# STM32F401R.net
KiCad netlist of a schematic drawn in Altium Designer
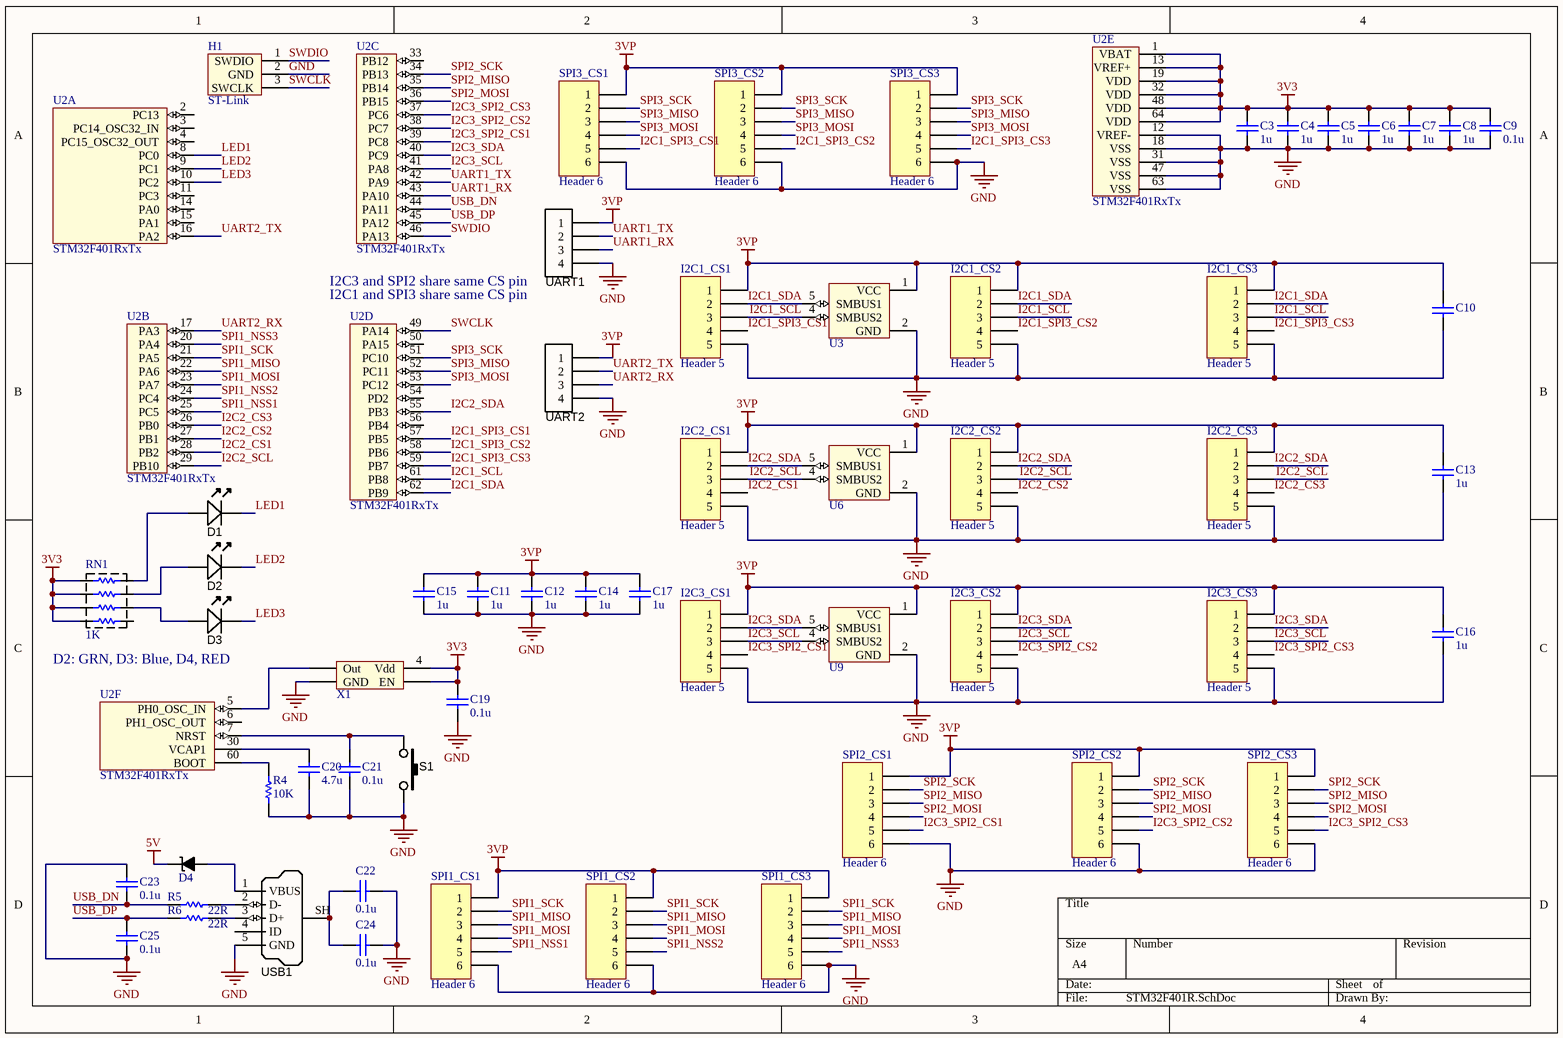
[diagram p0: STM32F401R.SchDoc]

(export (version "E")
  (design (tool "Eeschema 10.0.6"))
  (components
    (comp (ref "C3")
      (value "1u")
      (footprint "CAPC1608X90N")
      (description "Capacitor")
      (fields (field (name "Comment") "Cap") (field (name "PUBLISHER") "Altium Limited"))
      (libsource (lib "IOBoard_Low") (part "Cap"))
    )
    (comp (ref "C4")
      (value "1u")
      (footprint "CAPC1608X90N")
      (description "Capacitor")
      (fields (field (name "Comment") "Cap") (field (name "PUBLISHER") "Altium Limited"))
      (libsource (lib "IOBoard_Low") (part "Cap"))
    )
    (comp (ref "C5")
      (value "1u")
      (footprint "CAPC1608X90N")
      (description "Capacitor")
      (fields (field (name "Comment") "Cap") (field (name "PUBLISHER") "Altium Limited"))
      (libsource (lib "IOBoard_Low") (part "Cap"))
    )
    (comp (ref "C6")
      (value "1u")
      (footprint "CAPC1608X90N")
      (description "Capacitor")
      (fields (field (name "Comment") "Cap") (field (name "PUBLISHER") "Altium Limited"))
      (libsource (lib "IOBoard_Low") (part "Cap"))
    )
    (comp (ref "C7")
      (value "1u")
      (footprint "CAPC1608X90N")
      (description "Capacitor")
      (fields (field (name "Comment") "Cap") (field (name "PUBLISHER") "Altium Limited"))
      (libsource (lib "IOBoard_Low") (part "Cap"))
    )
    (comp (ref "C8")
      (value "1u")
      (footprint "CAPC1608X90N")
      (description "Capacitor")
      (fields (field (name "Comment") "Cap") (field (name "PUBLISHER") "Altium Limited"))
      (libsource (lib "IOBoard_Low") (part "Cap"))
    )
    (comp (ref "C9")
      (value "0.1u")
      (footprint "CAPC1608X90N")
      (description "Capacitor")
      (fields (field (name "Comment") "Cap") (field (name "PUBLISHER") "Altium Limited"))
      (libsource (lib "IOBoard_Low") (part "Cap"))
    )
    (comp (ref "C10")
      (value "Cap")
      (footprint "CAPC1608X90N")
      (description "Capacitor")
      (fields (field (name "PUBLISHER") "Altium Limited"))
      (libsource (lib "IOBoard_Low") (part "Cap"))
    )
    (comp (ref "C11")
      (value "1u")
      (footprint "CAPC1608X90N")
      (description "Capacitor")
      (fields (field (name "Comment") "Cap") (field (name "PUBLISHER") "Altium Limited"))
      (libsource (lib "IOBoard_Low") (part "Cap"))
    )
    (comp (ref "C12")
      (value "1u")
      (footprint "CAPC1608X90N")
      (description "Capacitor")
      (fields (field (name "Comment") "Cap") (field (name "PUBLISHER") "Altium Limited"))
      (libsource (lib "IOBoard_Low") (part "Cap"))
    )
    (comp (ref "C13")
      (value "1u")
      (footprint "CAPC1608X90N")
      (description "Capacitor")
      (fields (field (name "Comment") "Cap") (field (name "PUBLISHER") "Altium Limited"))
      (libsource (lib "IOBoard_Low") (part "Cap"))
    )
    (comp (ref "C14")
      (value "1u")
      (footprint "CAPC1608X90N")
      (description "Capacitor")
      (fields (field (name "Comment") "Cap") (field (name "PUBLISHER") "Altium Limited"))
      (libsource (lib "IOBoard_Low") (part "Cap"))
    )
    (comp (ref "C15")
      (value "1u")
      (footprint "CAPC1608X90N")
      (description "Capacitor")
      (fields (field (name "Comment") "Cap") (field (name "PUBLISHER") "Altium Limited"))
      (libsource (lib "IOBoard_Low") (part "Cap"))
    )
    (comp (ref "C16")
      (value "1u")
      (footprint "CAPC1608X90N")
      (description "Capacitor")
      (fields (field (name "Comment") "Cap") (field (name "PUBLISHER") "Altium Limited"))
      (libsource (lib "IOBoard_Low") (part "Cap"))
    )
    (comp (ref "C17")
      (value "1u")
      (footprint "CAPC1608X90N")
      (description "Capacitor")
      (fields (field (name "Comment") "Cap") (field (name "PUBLISHER") "Altium Limited"))
      (libsource (lib "IOBoard_Low") (part "Cap"))
    )
    (comp (ref "C19")
      (value "0.1u")
      (footprint "CAPC1608X90N")
      (description "Capacitor")
      (fields (field (name "Comment") "Cap") (field (name "PUBLISHER") "Altium Limited"))
      (libsource (lib "IOBoard_Low") (part "Cap"))
    )
    (comp (ref "C20")
      (value "4.7u")
      (footprint "CAPC1608X90N")
      (description "Capacitor")
      (fields (field (name "Comment") "Cap") (field (name "PUBLISHER") "Altium Limited"))
      (libsource (lib "IOBoard_Low") (part "Cap"))
    )
    (comp (ref "C21")
      (value "0.1u")
      (footprint "CAPC1608X90N")
      (description "Capacitor")
      (fields (field (name "Comment") "Cap") (field (name "PUBLISHER") "Altium Limited"))
      (libsource (lib "IOBoard_Low") (part "Cap"))
    )
    (comp (ref "C22")
      (value "0.1u")
      (footprint "CAPC1608X90N")
      (description "Capacitor")
      (fields (field (name "Comment") "Cap") (field (name "PUBLISHER") "Altium Limited"))
      (libsource (lib "IOBoard_Low") (part "Cap"))
    )
    (comp (ref "C23")
      (value "0.1u")
      (footprint "CAPC1608X90N")
      (description "Capacitor")
      (fields (field (name "Comment") "Cap") (field (name "PUBLISHER") "Altium Limited"))
      (libsource (lib "IOBoard_Low") (part "Cap"))
    )
    (comp (ref "C24")
      (value "0.1u")
      (footprint "CAPC1608X90N")
      (description "Capacitor")
      (fields (field (name "Comment") "Cap") (field (name "PUBLISHER") "Altium Limited"))
      (libsource (lib "IOBoard_Low") (part "Cap"))
    )
    (comp (ref "C25")
      (value "0.1u")
      (footprint "CAPC1608X90N")
      (description "Capacitor")
      (fields (field (name "Comment") "Cap") (field (name "PUBLISHER") "Altium Limited"))
      (libsource (lib "IOBoard_Low") (part "Cap"))
    )
    (comp (ref "D1")
      (value "LED_Green_GullWing")
      (footprint "LED-0805-A")
      (description "LED Gull-wing SMD High-intensity Green 450mcd 574nm")
      (libsource (lib "IOBoard") (part "LED_Green_GullWing"))
    )
    (comp (ref "D2")
      (value "LED_Green_GullWing")
      (footprint "LED-0805-A")
      (description "LED Gull-wing SMD High-intensity Green 450mcd 574nm")
      (libsource (lib "IOBoard") (part "LED_Green_GullWing"))
    )
    (comp (ref "D3")
      (value "LED_Green_GullWing")
      (footprint "LED-0805-A")
      (description "LED Gull-wing SMD High-intensity Green 450mcd 574nm")
      (libsource (lib "IOBoard") (part "LED_Green_GullWing"))
    )
    (comp (ref "D4")
      (value "MBRA210LT3G")
      (footprint "SMA")
      (description "Surface Mount  Schottky Power Rectifier")
      (fields (field (name "MANUFACTURER") "ON semiconductor"))
      (libsource (lib "IOBoard_Low") (part "MBRA210LT3G"))
    )
    (comp (ref "H1")
      (value "ST-Link")
      (footprint "ST-Link")
      (description "ST-Link header with silkscreen")
      (libsource (lib "IOBoard") (part "ST-Link"))
    )
    (comp (ref "I2C1_CS1")
      (value "Header 5")
      (footprint "HDR1X5")
      (description "Header, 5-Pin")
      (fields (field (name "PUBLISHER") "Altium Limited"))
      (libsource (lib "Miscellaneous Connectors") (part "Header 5"))
    )
    (comp (ref "I2C1_CS2")
      (value "Header 5")
      (footprint "HDR1X5")
      (description "Header, 5-Pin")
      (fields (field (name "PUBLISHER") "Altium Limited"))
      (libsource (lib "Miscellaneous Connectors") (part "Header 5"))
    )
    (comp (ref "I2C1_CS3")
      (value "Header 5")
      (footprint "HDR1X5")
      (description "Header, 5-Pin")
      (fields (field (name "PUBLISHER") "Altium Limited"))
      (libsource (lib "Miscellaneous Connectors") (part "Header 5"))
    )
    (comp (ref "I2C2_CS1")
      (value "Header 5")
      (footprint "HDR1X5")
      (description "Header, 5-Pin")
      (fields (field (name "PUBLISHER") "Altium Limited"))
      (libsource (lib "Miscellaneous Connectors") (part "Header 5"))
    )
    (comp (ref "I2C2_CS2")
      (value "Header 5")
      (footprint "HDR1X5")
      (description "Header, 5-Pin")
      (fields (field (name "PUBLISHER") "Altium Limited"))
      (libsource (lib "Miscellaneous Connectors") (part "Header 5"))
    )
    (comp (ref "I2C2_CS3")
      (value "Header 5")
      (footprint "HDR1X5")
      (description "Header, 5-Pin")
      (fields (field (name "PUBLISHER") "Altium Limited"))
      (libsource (lib "Miscellaneous Connectors") (part "Header 5"))
    )
    (comp (ref "I2C3_CS1")
      (value "Header 5")
      (footprint "HDR1X5")
      (description "Header, 5-Pin")
      (fields (field (name "PUBLISHER") "Altium Limited"))
      (libsource (lib "Miscellaneous Connectors") (part "Header 5"))
    )
    (comp (ref "I2C3_CS2")
      (value "Header 5")
      (footprint "HDR1X5")
      (description "Header, 5-Pin")
      (fields (field (name "PUBLISHER") "Altium Limited"))
      (libsource (lib "Miscellaneous Connectors") (part "Header 5"))
    )
    (comp (ref "I2C3_CS3")
      (value "Header 5")
      (footprint "HDR1X5")
      (description "Header, 5-Pin")
      (fields (field (name "PUBLISHER") "Altium Limited"))
      (libsource (lib "Miscellaneous Connectors") (part "Header 5"))
    )
    (comp (ref "R4")
      (value "10K")
      (footprint "RESC1608X55N")
      (description "Resistor")
      (fields (field (name "Comment") "Res1") (field (name "PUBLISHER") "Altium Limited"))
      (libsource (lib "IOBoard_Low") (part "Res1"))
    )
    (comp (ref "R5")
      (value "22R")
      (footprint "RESC1608X55N")
      (description "Resistor")
      (fields (field (name "Comment") "Res1") (field (name "PUBLISHER") "Altium Limited"))
      (libsource (lib "IOBoard_Low") (part "Res1"))
    )
    (comp (ref "R6")
      (value "22R")
      (footprint "RESC1608X55N")
      (description "Resistor")
      (fields (field (name "Comment") "Res1") (field (name "PUBLISHER") "Altium Limited"))
      (libsource (lib "IOBoard_Low") (part "Res1"))
    )
    (comp (ref "RN1")
      (value "1K")
      (footprint "RESCAXS50P160X320X70-8N")
      (fields (field (name "Comment") "resistor network"))
      (libsource (lib "IOBoard") (part "RES_NET"))
    )
    (comp (ref "S1")
      (value "SW_THT_PB_4.3mm")
      (footprint "TACT_SWT-SMD-4.4")
      (description "Switch, tact, 4.3mm stem")
      (libsource (lib "IOBoard") (part "SW_THT_PB_4.3mm"))
    )
    (comp (ref "SPI1_CS1")
      (value "Header 6")
      (footprint "HDR1X6")
      (description "Header, 6-Pin")
      (fields (field (name "PUBLISHER") "Altium Limited"))
      (libsource (lib "Miscellaneous Connectors") (part "Header 6"))
    )
    (comp (ref "SPI1_CS2")
      (value "Header 6")
      (footprint "HDR1X6")
      (description "Header, 6-Pin")
      (fields (field (name "PUBLISHER") "Altium Limited"))
      (libsource (lib "Miscellaneous Connectors") (part "Header 6"))
    )
    (comp (ref "SPI1_CS3")
      (value "Header 6")
      (footprint "HDR1X6")
      (description "Header, 6-Pin")
      (fields (field (name "PUBLISHER") "Altium Limited"))
      (libsource (lib "Miscellaneous Connectors") (part "Header 6"))
    )
    (comp (ref "SPI2_CS1")
      (value "Header 6")
      (footprint "HDR1X6")
      (description "Header, 6-Pin")
      (fields (field (name "PUBLISHER") "Altium Limited"))
      (libsource (lib "Miscellaneous Connectors") (part "Header 6"))
    )
    (comp (ref "SPI2_CS2")
      (value "Header 6")
      (footprint "HDR1X6")
      (description "Header, 6-Pin")
      (fields (field (name "PUBLISHER") "Altium Limited"))
      (libsource (lib "Miscellaneous Connectors") (part "Header 6"))
    )
    (comp (ref "SPI2_CS3")
      (value "Header 6")
      (footprint "HDR1X6")
      (description "Header, 6-Pin")
      (fields (field (name "PUBLISHER") "Altium Limited"))
      (libsource (lib "Miscellaneous Connectors") (part "Header 6"))
    )
    (comp (ref "SPI3_CS1")
      (value "Header 6")
      (footprint "HDR1X6")
      (description "Header, 6-Pin")
      (fields (field (name "PUBLISHER") "Altium Limited"))
      (libsource (lib "Miscellaneous Connectors") (part "Header 6"))
    )
    (comp (ref "SPI3_CS2")
      (value "Header 6")
      (footprint "HDR1X6")
      (description "Header, 6-Pin")
      (fields (field (name "PUBLISHER") "Altium Limited"))
      (libsource (lib "Miscellaneous Connectors") (part "Header 6"))
    )
    (comp (ref "SPI3_CS3")
      (value "Header 6")
      (footprint "HDR1X6")
      (description "Header, 6-Pin")
      (fields (field (name "PUBLISHER") "Altium Limited"))
      (libsource (lib "Miscellaneous Connectors") (part "Header 6"))
    )
    (comp (ref "U2")
      (value "STM32F401RxTx")
      (footprint "LQFP64")
      (libsource (lib "IOBoard") (part "STM32F401RxTx"))
    )
    (comp (ref "U3") (value "LTC1694") (footprint "SOT23-5") (libsource (lib "IOBoard") (part "LTC1694")))
    (comp (ref "U6") (value "LTC1694") (footprint "SOT23-5") (libsource (lib "IOBoard") (part "LTC1694")))
    (comp (ref "U9") (value "LTC1694") (footprint "SOT23-5") (libsource (lib "IOBoard") (part "LTC1694")))
    (comp (ref "UART1")
      (value "Programmer")
      (footprint "HDR1X4_2.54MMP")
      (description "Header 4-pin")
      (libsource (lib "IOBoard") (part "Header4P"))
    )
    (comp (ref "UART2")
      (value "Programmer")
      (footprint "HDR1X4_2.54MMP")
      (description "Header 4-pin")
      (libsource (lib "IOBoard") (part "Header4P"))
    )
    (comp (ref "USB1")
      (value "USB Micro Type B")
      (footprint "USB_MICRO-B")
      (description "Connector SMD USB Micro Type B middle mount")
      (libsource (lib "IOBoard") (part "USB_Micro_TypeB"))
    )
    (comp (ref "X1")
      (value "ASV-8.000MHZ-EJ-T")
      (footprint "ASV SERIES")
      (description "3.3Vdc HCMOS SMD Crystal Clock Oscillator")
      (fields (field (name "MANUFACTURER") "Abracon"))
      (libsource (lib "IOBoard") (part "ASV-8.000MHZ-EJ-T"))
    )
  )
  (nets
    (net (code "1") (name "/I2C1_SCL") (class "Default")
      (node (ref "I2C1_CS1") (pin "3") (pinfunction "3_3") (pintype "passive"))
      (node (ref "I2C1_CS2") (pin "3") (pinfunction "3_3") (pintype "passive"))
      (node (ref "I2C1_CS3") (pin "3") (pinfunction "3_3") (pintype "passive"))
      (node (ref "U2") (pin "61") (pinfunction "PB8_61") (pintype "bidirectional"))
      (node (ref "U3") (pin "4") (pinfunction "SMBUS2_4") (pintype "bidirectional"))
    )
    (net (code "2") (name "/I2C1_SDA") (class "Default")
      (node (ref "I2C1_CS1") (pin "2") (pinfunction "2_2") (pintype "passive"))
      (node (ref "I2C1_CS2") (pin "2") (pinfunction "2_2") (pintype "passive"))
      (node (ref "I2C1_CS3") (pin "2") (pinfunction "2_2") (pintype "passive"))
      (node (ref "U2") (pin "62") (pinfunction "PB9_62") (pintype "bidirectional"))
      (node (ref "U3") (pin "5") (pinfunction "SMBUS1_5") (pintype "bidirectional"))
    )
    (net (code "3") (name "/I2C1_SPI3_CS1") (class "Default")
      (node (ref "I2C1_CS1") (pin "4") (pinfunction "4_4") (pintype "passive"))
      (node (ref "SPI3_CS1") (pin "5") (pinfunction "5_5") (pintype "passive"))
      (node (ref "U2") (pin "57") (pinfunction "PB5_57") (pintype "bidirectional"))
    )
    (net (code "4") (name "/I2C1_SPI3_CS2") (class "Default")
      (node (ref "I2C1_CS2") (pin "4") (pinfunction "4_4") (pintype "passive"))
      (node (ref "SPI3_CS2") (pin "5") (pinfunction "5_5") (pintype "passive"))
      (node (ref "U2") (pin "58") (pinfunction "PB6_58") (pintype "bidirectional"))
    )
    (net (code "5") (name "/I2C1_SPI3_CS3") (class "Default")
      (node (ref "I2C1_CS3") (pin "4") (pinfunction "4_4") (pintype "passive"))
      (node (ref "SPI3_CS3") (pin "5") (pinfunction "5_5") (pintype "passive"))
      (node (ref "U2") (pin "59") (pinfunction "PB7_59") (pintype "bidirectional"))
    )
    (net (code "6") (name "/I2C2_CS1") (class "Default")
      (node (ref "I2C2_CS1") (pin "4") (pinfunction "4_4") (pintype "passive"))
      (node (ref "U2") (pin "28") (pinfunction "PB2_28") (pintype "bidirectional"))
    )
    (net (code "7") (name "/I2C2_CS2") (class "Default")
      (node (ref "I2C2_CS2") (pin "4") (pinfunction "4_4") (pintype "passive"))
      (node (ref "U2") (pin "27") (pinfunction "PB1_27") (pintype "bidirectional"))
    )
    (net (code "8") (name "/I2C2_CS3") (class "Default")
      (node (ref "I2C2_CS3") (pin "4") (pinfunction "4_4") (pintype "passive"))
      (node (ref "U2") (pin "26") (pinfunction "PB0_26") (pintype "bidirectional"))
    )
    (net (code "9") (name "/I2C2_SCL") (class "Default")
      (node (ref "I2C2_CS1") (pin "3") (pinfunction "3_3") (pintype "passive"))
      (node (ref "I2C2_CS2") (pin "3") (pinfunction "3_3") (pintype "passive"))
      (node (ref "I2C2_CS3") (pin "3") (pinfunction "3_3") (pintype "passive"))
      (node (ref "U2") (pin "29") (pinfunction "PB10_29") (pintype "bidirectional"))
      (node (ref "U6") (pin "4") (pinfunction "SMBUS2_4") (pintype "bidirectional"))
    )
    (net (code "10") (name "/I2C2_SDA") (class "Default")
      (node (ref "I2C2_CS1") (pin "2") (pinfunction "2_2") (pintype "passive"))
      (node (ref "I2C2_CS2") (pin "2") (pinfunction "2_2") (pintype "passive"))
      (node (ref "I2C2_CS3") (pin "2") (pinfunction "2_2") (pintype "passive"))
      (node (ref "U2") (pin "55") (pinfunction "PB3_55") (pintype "bidirectional"))
      (node (ref "U6") (pin "5") (pinfunction "SMBUS1_5") (pintype "bidirectional"))
    )
    (net (code "11") (name "/I2C3_SCL") (class "Default")
      (node (ref "I2C3_CS1") (pin "3") (pinfunction "3_3") (pintype "passive"))
      (node (ref "I2C3_CS2") (pin "3") (pinfunction "3_3") (pintype "passive"))
      (node (ref "I2C3_CS3") (pin "3") (pinfunction "3_3") (pintype "passive"))
      (node (ref "U2") (pin "41") (pinfunction "PA8_41") (pintype "bidirectional"))
      (node (ref "U9") (pin "4") (pinfunction "SMBUS2_4") (pintype "bidirectional"))
    )
    (net (code "12") (name "/I2C3_SDA") (class "Default")
      (node (ref "I2C3_CS1") (pin "2") (pinfunction "2_2") (pintype "passive"))
      (node (ref "I2C3_CS2") (pin "2") (pinfunction "2_2") (pintype "passive"))
      (node (ref "I2C3_CS3") (pin "2") (pinfunction "2_2") (pintype "passive"))
      (node (ref "U2") (pin "40") (pinfunction "PC9_40") (pintype "bidirectional"))
      (node (ref "U9") (pin "5") (pinfunction "SMBUS1_5") (pintype "bidirectional"))
    )
    (net (code "13") (name "/I2C3_SPI2_CS1") (class "Default")
      (node (ref "I2C3_CS1") (pin "4") (pinfunction "4_4") (pintype "passive"))
      (node (ref "SPI2_CS1") (pin "5") (pinfunction "5_5") (pintype "passive"))
      (node (ref "U2") (pin "39") (pinfunction "PC8_39") (pintype "bidirectional"))
    )
    (net (code "14") (name "/I2C3_SPI2_CS2") (class "Default")
      (node (ref "I2C3_CS2") (pin "4") (pinfunction "4_4") (pintype "passive"))
      (node (ref "SPI2_CS2") (pin "5") (pinfunction "5_5") (pintype "passive"))
      (node (ref "U2") (pin "38") (pinfunction "PC7_38") (pintype "bidirectional"))
    )
    (net (code "15") (name "/I2C3_SPI2_CS3") (class "Default")
      (node (ref "I2C3_CS3") (pin "4") (pinfunction "4_4") (pintype "passive"))
      (node (ref "SPI2_CS3") (pin "5") (pinfunction "5_5") (pintype "passive"))
      (node (ref "U2") (pin "37") (pinfunction "PC6_37") (pintype "bidirectional"))
    )
    (net (code "16") (name "/LED1") (class "Default")
      (node (ref "D1") (pin "K") (pinfunction "K_K") (pintype "passive"))
      (node (ref "U2") (pin "8") (pinfunction "PC0_8") (pintype "bidirectional"))
    )
    (net (code "17") (name "/LED2") (class "Default")
      (node (ref "D2") (pin "K") (pinfunction "K_K") (pintype "passive"))
      (node (ref "U2") (pin "9") (pinfunction "PC1_9") (pintype "bidirectional"))
    )
    (net (code "18") (name "/LED3") (class "Default")
      (node (ref "D3") (pin "K") (pinfunction "K_K") (pintype "passive"))
      (node (ref "U2") (pin "10") (pinfunction "PC2_10") (pintype "bidirectional"))
    )
    (net (code "19") (name "/SPI1_MISO") (class "Default")
      (node (ref "SPI1_CS1") (pin "3") (pinfunction "3_3") (pintype "passive"))
      (node (ref "SPI1_CS2") (pin "3") (pinfunction "3_3") (pintype "passive"))
      (node (ref "SPI1_CS3") (pin "3") (pinfunction "3_3") (pintype "passive"))
      (node (ref "U2") (pin "22") (pinfunction "PA6_22") (pintype "bidirectional"))
    )
    (net (code "20") (name "/SPI1_MOSI") (class "Default")
      (node (ref "SPI1_CS1") (pin "4") (pinfunction "4_4") (pintype "passive"))
      (node (ref "SPI1_CS2") (pin "4") (pinfunction "4_4") (pintype "passive"))
      (node (ref "SPI1_CS3") (pin "4") (pinfunction "4_4") (pintype "passive"))
      (node (ref "U2") (pin "23") (pinfunction "PA7_23") (pintype "bidirectional"))
    )
    (net (code "21") (name "/SPI1_NSS1") (class "Default")
      (node (ref "SPI1_CS1") (pin "5") (pinfunction "5_5") (pintype "passive"))
      (node (ref "U2") (pin "25") (pinfunction "PC5_25") (pintype "bidirectional"))
    )
    (net (code "22") (name "/SPI1_NSS2") (class "Default")
      (node (ref "SPI1_CS2") (pin "5") (pinfunction "5_5") (pintype "passive"))
      (node (ref "U2") (pin "24") (pinfunction "PC4_24") (pintype "bidirectional"))
    )
    (net (code "23") (name "/SPI1_NSS3") (class "Default")
      (node (ref "SPI1_CS3") (pin "5") (pinfunction "5_5") (pintype "passive"))
      (node (ref "U2") (pin "20") (pinfunction "PA4_20") (pintype "bidirectional"))
    )
    (net (code "24") (name "/SPI1_SCK") (class "Default")
      (node (ref "SPI1_CS1") (pin "2") (pinfunction "2_2") (pintype "passive"))
      (node (ref "SPI1_CS2") (pin "2") (pinfunction "2_2") (pintype "passive"))
      (node (ref "SPI1_CS3") (pin "2") (pinfunction "2_2") (pintype "passive"))
      (node (ref "U2") (pin "21") (pinfunction "PA5_21") (pintype "bidirectional"))
    )
    (net (code "25") (name "/SPI2_MISO") (class "Default")
      (node (ref "SPI2_CS1") (pin "3") (pinfunction "3_3") (pintype "passive"))
      (node (ref "SPI2_CS2") (pin "3") (pinfunction "3_3") (pintype "passive"))
      (node (ref "SPI2_CS3") (pin "3") (pinfunction "3_3") (pintype "passive"))
      (node (ref "U2") (pin "35") (pinfunction "PB14_35") (pintype "bidirectional"))
    )
    (net (code "26") (name "/SPI2_MOSI") (class "Default")
      (node (ref "SPI2_CS1") (pin "4") (pinfunction "4_4") (pintype "passive"))
      (node (ref "SPI2_CS2") (pin "4") (pinfunction "4_4") (pintype "passive"))
      (node (ref "SPI2_CS3") (pin "4") (pinfunction "4_4") (pintype "passive"))
      (node (ref "U2") (pin "36") (pinfunction "PB15_36") (pintype "bidirectional"))
    )
    (net (code "27") (name "/SPI2_SCK") (class "Default")
      (node (ref "SPI2_CS1") (pin "2") (pinfunction "2_2") (pintype "passive"))
      (node (ref "SPI2_CS2") (pin "2") (pinfunction "2_2") (pintype "passive"))
      (node (ref "SPI2_CS3") (pin "2") (pinfunction "2_2") (pintype "passive"))
      (node (ref "U2") (pin "34") (pinfunction "PB13_34") (pintype "bidirectional"))
    )
    (net (code "28") (name "/SPI3_MISO") (class "Default")
      (node (ref "SPI3_CS1") (pin "3") (pinfunction "3_3") (pintype "passive"))
      (node (ref "SPI3_CS2") (pin "3") (pinfunction "3_3") (pintype "passive"))
      (node (ref "SPI3_CS3") (pin "3") (pinfunction "3_3") (pintype "passive"))
      (node (ref "U2") (pin "52") (pinfunction "PC11_52") (pintype "bidirectional"))
    )
    (net (code "29") (name "/SPI3_MOSI") (class "Default")
      (node (ref "SPI3_CS1") (pin "4") (pinfunction "4_4") (pintype "passive"))
      (node (ref "SPI3_CS2") (pin "4") (pinfunction "4_4") (pintype "passive"))
      (node (ref "SPI3_CS3") (pin "4") (pinfunction "4_4") (pintype "passive"))
      (node (ref "U2") (pin "53") (pinfunction "PC12_53") (pintype "bidirectional"))
    )
    (net (code "30") (name "/SPI3_SCK") (class "Default")
      (node (ref "SPI3_CS1") (pin "2") (pinfunction "2_2") (pintype "passive"))
      (node (ref "SPI3_CS2") (pin "2") (pinfunction "2_2") (pintype "passive"))
      (node (ref "SPI3_CS3") (pin "2") (pinfunction "2_2") (pintype "passive"))
      (node (ref "U2") (pin "51") (pinfunction "PC10_51") (pintype "bidirectional"))
    )
    (net (code "31") (name "/SWCLK") (class "Default")
      (node (ref "H1") (pin "3") (pinfunction "SWCLK_3") (pintype "power_in"))
      (node (ref "U2") (pin "49") (pinfunction "PA14_49") (pintype "bidirectional"))
    )
    (net (code "32") (name "/SWDIO") (class "Default")
      (node (ref "H1") (pin "1") (pinfunction "SWDIO_1") (pintype "power_in"))
      (node (ref "U2") (pin "46") (pinfunction "PA13_46") (pintype "bidirectional"))
    )
    (net (code "33") (name "/UART1_RX") (class "Default")
      (node (ref "U2") (pin "43") (pinfunction "PA10_43") (pintype "bidirectional"))
      (node (ref "UART1") (pin "3") (pinfunction "3_3") (pintype "passive"))
    )
    (net (code "34") (name "/UART1_TX") (class "Default")
      (node (ref "U2") (pin "42") (pinfunction "PA9_42") (pintype "bidirectional"))
      (node (ref "UART1") (pin "2") (pinfunction "2_2") (pintype "passive"))
    )
    (net (code "35") (name "/UART2_RX") (class "Default")
      (node (ref "U2") (pin "17") (pinfunction "PA3_17") (pintype "bidirectional"))
      (node (ref "UART2") (pin "3") (pinfunction "3_3") (pintype "passive"))
    )
    (net (code "36") (name "/UART2_TX") (class "Default")
      (node (ref "U2") (pin "16") (pinfunction "PA2_16") (pintype "bidirectional"))
      (node (ref "UART2") (pin "2") (pinfunction "2_2") (pintype "passive"))
    )
    (net (code "37") (name "/USB_DN") (class "Default")
      (node (ref "C23") (pin "1") (pinfunction "1_1") (pintype "passive"))
      (node (ref "R5") (pin "1") (pinfunction "1_1") (pintype "passive"))
      (node (ref "U2") (pin "44") (pinfunction "PA11_44") (pintype "bidirectional"))
    )
    (net (code "38") (name "/USB_DP") (class "Default")
      (node (ref "C25") (pin "2") (pinfunction "2_2") (pintype "passive"))
      (node (ref "R6") (pin "1") (pinfunction "1_1") (pintype "passive"))
      (node (ref "U2") (pin "45") (pinfunction "PA12_45") (pintype "bidirectional"))
    )
    (net (code "39") (name "3V3") (class "Default")
      (node (ref "C19") (pin "2") (pinfunction "2_2") (pintype "passive"))
      (node (ref "C3") (pin "2") (pinfunction "2_2") (pintype "passive"))
      (node (ref "C4") (pin "2") (pinfunction "2_2") (pintype "passive"))
      (node (ref "C5") (pin "2") (pinfunction "2_2") (pintype "passive"))
      (node (ref "C6") (pin "2") (pinfunction "2_2") (pintype "passive"))
      (node (ref "C7") (pin "2") (pinfunction "2_2") (pintype "passive"))
      (node (ref "C8") (pin "2") (pinfunction "2_2") (pintype "passive"))
      (node (ref "C9") (pin "2") (pinfunction "2_2") (pintype "passive"))
      (node (ref "RN1") (pin "1") (pinfunction "1_1") (pintype "power_in"))
      (node (ref "RN1") (pin "2") (pinfunction "2_2") (pintype "power_in"))
      (node (ref "RN1") (pin "3") (pinfunction "3_3") (pintype "power_in"))
      (node (ref "RN1") (pin "4") (pinfunction "4_4") (pintype "power_in"))
      (node (ref "U2") (pin "1") (pinfunction "VBAT_1") (pintype "power_in"))
      (node (ref "U2") (pin "13") (pinfunction "VREF+_13") (pintype "power_in"))
      (node (ref "U2") (pin "19") (pinfunction "VDD_19") (pintype "power_in"))
      (node (ref "U2") (pin "32") (pinfunction "VDD_32") (pintype "power_in"))
      (node (ref "U2") (pin "48") (pinfunction "VDD_48") (pintype "power_in"))
      (node (ref "U2") (pin "64") (pinfunction "VDD_64") (pintype "power_in"))
      (node (ref "X1") (pin "1") (pinfunction "EN_1") (pintype "passive"))
      (node (ref "X1") (pin "4") (pinfunction "Vdd_4") (pintype "passive"))
    )
    (net (code "40") (name "3VP") (class "Default")
      (node (ref "C10") (pin "2") (pinfunction "2_2") (pintype "passive"))
      (node (ref "C11") (pin "2") (pinfunction "2_2") (pintype "passive"))
      (node (ref "C12") (pin "2") (pinfunction "2_2") (pintype "passive"))
      (node (ref "C13") (pin "2") (pinfunction "2_2") (pintype "passive"))
      (node (ref "C14") (pin "2") (pinfunction "2_2") (pintype "passive"))
      (node (ref "C15") (pin "2") (pinfunction "2_2") (pintype "passive"))
      (node (ref "C16") (pin "2") (pinfunction "2_2") (pintype "passive"))
      (node (ref "C17") (pin "2") (pinfunction "2_2") (pintype "passive"))
      (node (ref "I2C1_CS1") (pin "1") (pinfunction "1_1") (pintype "passive"))
      (node (ref "I2C1_CS2") (pin "1") (pinfunction "1_1") (pintype "passive"))
      (node (ref "I2C1_CS3") (pin "1") (pinfunction "1_1") (pintype "passive"))
      (node (ref "I2C2_CS1") (pin "1") (pinfunction "1_1") (pintype "passive"))
      (node (ref "I2C2_CS2") (pin "1") (pinfunction "1_1") (pintype "passive"))
      (node (ref "I2C2_CS3") (pin "1") (pinfunction "1_1") (pintype "passive"))
      (node (ref "I2C3_CS1") (pin "1") (pinfunction "1_1") (pintype "passive"))
      (node (ref "I2C3_CS2") (pin "1") (pinfunction "1_1") (pintype "passive"))
      (node (ref "I2C3_CS3") (pin "1") (pinfunction "1_1") (pintype "passive"))
      (node (ref "SPI1_CS1") (pin "1") (pinfunction "1_1") (pintype "passive"))
      (node (ref "SPI1_CS2") (pin "1") (pinfunction "1_1") (pintype "passive"))
      (node (ref "SPI1_CS3") (pin "1") (pinfunction "1_1") (pintype "passive"))
      (node (ref "SPI2_CS1") (pin "1") (pinfunction "1_1") (pintype "passive"))
      (node (ref "SPI2_CS2") (pin "1") (pinfunction "1_1") (pintype "passive"))
      (node (ref "SPI2_CS3") (pin "1") (pinfunction "1_1") (pintype "passive"))
      (node (ref "SPI3_CS1") (pin "1") (pinfunction "1_1") (pintype "passive"))
      (node (ref "SPI3_CS2") (pin "1") (pinfunction "1_1") (pintype "passive"))
      (node (ref "SPI3_CS3") (pin "1") (pinfunction "1_1") (pintype "passive"))
      (node (ref "U3") (pin "1") (pinfunction "VCC_1") (pintype "power_in"))
      (node (ref "U6") (pin "1") (pinfunction "VCC_1") (pintype "power_in"))
      (node (ref "U9") (pin "1") (pinfunction "VCC_1") (pintype "power_in"))
      (node (ref "UART1") (pin "1") (pinfunction "1_1") (pintype "passive"))
      (node (ref "UART2") (pin "1") (pinfunction "1_1") (pintype "passive"))
    )
    (net (code "41") (name "5V") (class "Default")
      (node (ref "D4") (pin "K") (pinfunction "Cathode_K") (pintype "passive"))
    )
    (net (code "42") (name "GND") (class "Default")
      (node (ref "C10") (pin "1") (pinfunction "1_1") (pintype "passive"))
      (node (ref "C11") (pin "1") (pinfunction "1_1") (pintype "passive"))
      (node (ref "C12") (pin "1") (pinfunction "1_1") (pintype "passive"))
      (node (ref "C13") (pin "1") (pinfunction "1_1") (pintype "passive"))
      (node (ref "C14") (pin "1") (pinfunction "1_1") (pintype "passive"))
      (node (ref "C15") (pin "1") (pinfunction "1_1") (pintype "passive"))
      (node (ref "C16") (pin "1") (pinfunction "1_1") (pintype "passive"))
      (node (ref "C17") (pin "1") (pinfunction "1_1") (pintype "passive"))
      (node (ref "C19") (pin "1") (pinfunction "1_1") (pintype "passive"))
      (node (ref "C20") (pin "1") (pinfunction "1_1") (pintype "passive"))
      (node (ref "C21") (pin "1") (pinfunction "1_1") (pintype "passive"))
      (node (ref "C22") (pin "2") (pinfunction "2_2") (pintype "passive"))
      (node (ref "C23") (pin "2") (pinfunction "2_2") (pintype "passive"))
      (node (ref "C24") (pin "2") (pinfunction "2_2") (pintype "passive"))
      (node (ref "C25") (pin "1") (pinfunction "1_1") (pintype "passive"))
      (node (ref "C3") (pin "1") (pinfunction "1_1") (pintype "passive"))
      (node (ref "C4") (pin "1") (pinfunction "1_1") (pintype "passive"))
      (node (ref "C5") (pin "1") (pinfunction "1_1") (pintype "passive"))
      (node (ref "C6") (pin "1") (pinfunction "1_1") (pintype "passive"))
      (node (ref "C7") (pin "1") (pinfunction "1_1") (pintype "passive"))
      (node (ref "C8") (pin "1") (pinfunction "1_1") (pintype "passive"))
      (node (ref "C9") (pin "1") (pinfunction "1_1") (pintype "passive"))
      (node (ref "H1") (pin "2") (pinfunction "GND_2") (pintype "power_in"))
      (node (ref "I2C1_CS1") (pin "5") (pinfunction "5_5") (pintype "passive"))
      (node (ref "I2C1_CS2") (pin "5") (pinfunction "5_5") (pintype "passive"))
      (node (ref "I2C1_CS3") (pin "5") (pinfunction "5_5") (pintype "passive"))
      (node (ref "I2C2_CS1") (pin "5") (pinfunction "5_5") (pintype "passive"))
      (node (ref "I2C2_CS2") (pin "5") (pinfunction "5_5") (pintype "passive"))
      (node (ref "I2C2_CS3") (pin "5") (pinfunction "5_5") (pintype "passive"))
      (node (ref "I2C3_CS1") (pin "5") (pinfunction "5_5") (pintype "passive"))
      (node (ref "I2C3_CS2") (pin "5") (pinfunction "5_5") (pintype "passive"))
      (node (ref "I2C3_CS3") (pin "5") (pinfunction "5_5") (pintype "passive"))
      (node (ref "R4") (pin "1") (pinfunction "1_1") (pintype "passive"))
      (node (ref "S1") (pin "2") (pintype "passive"))
      (node (ref "SPI1_CS1") (pin "6") (pinfunction "6_6") (pintype "passive"))
      (node (ref "SPI1_CS2") (pin "6") (pinfunction "6_6") (pintype "passive"))
      (node (ref "SPI1_CS3") (pin "6") (pinfunction "6_6") (pintype "passive"))
      (node (ref "SPI2_CS1") (pin "6") (pinfunction "6_6") (pintype "passive"))
      (node (ref "SPI2_CS2") (pin "6") (pinfunction "6_6") (pintype "passive"))
      (node (ref "SPI2_CS3") (pin "6") (pinfunction "6_6") (pintype "passive"))
      (node (ref "SPI3_CS1") (pin "6") (pinfunction "6_6") (pintype "passive"))
      (node (ref "SPI3_CS2") (pin "6") (pinfunction "6_6") (pintype "passive"))
      (node (ref "SPI3_CS3") (pin "6") (pinfunction "6_6") (pintype "passive"))
      (node (ref "U2") (pin "12") (pinfunction "VREF-_12") (pintype "power_in"))
      (node (ref "U2") (pin "18") (pinfunction "VSS_18") (pintype "power_in"))
      (node (ref "U2") (pin "31") (pinfunction "VSS_31") (pintype "power_in"))
      (node (ref "U2") (pin "47") (pinfunction "VSS_47") (pintype "power_in"))
      (node (ref "U2") (pin "63") (pinfunction "VSS_63") (pintype "power_in"))
      (node (ref "U3") (pin "2") (pinfunction "GND_2") (pintype "power_in"))
      (node (ref "U6") (pin "2") (pinfunction "GND_2") (pintype "power_in"))
      (node (ref "U9") (pin "2") (pinfunction "GND_2") (pintype "power_in"))
      (node (ref "UART1") (pin "4") (pinfunction "4_4") (pintype "passive"))
      (node (ref "UART2") (pin "4") (pinfunction "4_4") (pintype "passive"))
      (node (ref "USB1") (pin "5") (pinfunction "GND_5") (pintype "power_in"))
      (node (ref "X1") (pin "2") (pinfunction "GND_2") (pintype "passive"))
    )
    (net (code "43") (name "Net-(D1-PadA)") (class "Default")
      (node (ref "D1") (pin "A") (pinfunction "A_A") (pintype "passive"))
      (node (ref "RN1") (pin "8") (pinfunction "8_8") (pintype "power_in"))
    )
    (net (code "44") (name "Net-(D2-PadA)") (class "Default")
      (node (ref "D2") (pin "A") (pinfunction "A_A") (pintype "passive"))
      (node (ref "RN1") (pin "7") (pinfunction "7_7") (pintype "power_in"))
    )
    (net (code "45") (name "Net-(D3-PadA)") (class "Default")
      (node (ref "D3") (pin "A") (pinfunction "A_A") (pintype "passive"))
      (node (ref "RN1") (pin "6") (pinfunction "6_6") (pintype "power_in"))
    )
    (net (code "46") (name "Net-(D4-Anode)") (class "Default")
      (node (ref "D4") (pin "A") (pinfunction "Anode_A") (pintype "passive"))
      (node (ref "USB1") (pin "1") (pinfunction "VBUS_1") (pintype "power_in"))
    )
    (net (code "47") (name "Net-(U2F-BOOT)") (class "Default")
      (node (ref "R4") (pin "2") (pinfunction "2_2") (pintype "passive"))
      (node (ref "U2") (pin "60") (pinfunction "BOOT_60") (pintype "power_in"))
    )
    (net (code "48") (name "Net-(U2F-NRST)") (class "Default")
      (node (ref "C21") (pin "2") (pinfunction "2_2") (pintype "passive"))
      (node (ref "S1") (pin "1") (pintype "passive"))
      (node (ref "U2") (pin "7") (pinfunction "NRST_7") (pintype "bidirectional"))
    )
    (net (code "49") (name "Net-(U2F-PH0_OSC_IN)") (class "Default")
      (node (ref "U2") (pin "5") (pinfunction "PH0_OSC_IN_5") (pintype "bidirectional"))
      (node (ref "X1") (pin "3") (pinfunction "Out_3") (pintype "passive"))
    )
    (net (code "50") (name "Net-(U2F-VCAP1)") (class "Default")
      (node (ref "C20") (pin "2") (pinfunction "2_2") (pintype "passive"))
      (node (ref "U2") (pin "30") (pinfunction "VCAP1_30") (pintype "power_in"))
    )
    (net (code "51") (name "Net-(USB1-D+)") (class "Default")
      (node (ref "R6") (pin "2") (pinfunction "2_2") (pintype "passive"))
      (node (ref "USB1") (pin "3") (pinfunction "D+_3") (pintype "bidirectional"))
    )
    (net (code "52") (name "Net-(USB1-D-)") (class "Default")
      (node (ref "R5") (pin "2") (pinfunction "2_2") (pintype "passive"))
      (node (ref "USB1") (pin "2") (pinfunction "D-_2") (pintype "bidirectional"))
    )
    (net (code "53") (name "Net-(USB1-Shell)") (class "Default")
      (node (ref "C22") (pin "1") (pinfunction "1_1") (pintype "passive"))
      (node (ref "C24") (pin "1") (pinfunction "1_1") (pintype "passive"))
      (node (ref "USB1") (pin "SH") (pinfunction "Shell_SH") (pintype "passive"))
    )
    (net (code "54") (name "unconnected-(RN1-Pad5)") (class "Default")
      (node (ref "RN1") (pin "5") (pinfunction "5_5") (pintype "power_in"))
    )
    (net (code "55") (name "unconnected-(U2A-PA0-Pad14)") (class "Default")
      (node (ref "U2") (pin "14") (pinfunction "PA0_14") (pintype "bidirectional"))
    )
    (net (code "56") (name "unconnected-(U2A-PA1-Pad15)") (class "Default")
      (node (ref "U2") (pin "15") (pinfunction "PA1_15") (pintype "bidirectional"))
    )
    (net (code "57") (name "unconnected-(U2A-PC3-Pad11)") (class "Default")
      (node (ref "U2") (pin "11") (pinfunction "PC3_11") (pintype "bidirectional"))
    )
    (net (code "58") (name "unconnected-(U2A-PC13-Pad2)") (class "Default")
      (node (ref "U2") (pin "2") (pinfunction "PC13_2") (pintype "bidirectional"))
    )
    (net (code "59") (name "unconnected-(U2A-PC14_OSC32_IN-Pad3)") (class "Default")
      (node (ref "U2") (pin "3") (pinfunction "PC14_OSC32_IN_3") (pintype "bidirectional"))
    )
    (net (code "60") (name "unconnected-(U2A-PC15_OSC32_OUT-Pad4)") (class "Default")
      (node (ref "U2") (pin "4") (pinfunction "PC15_OSC32_OUT_4") (pintype "bidirectional"))
    )
    (net (code "61") (name "unconnected-(U2C-PB12-Pad33)") (class "Default")
      (node (ref "U2") (pin "33") (pinfunction "PB12_33") (pintype "bidirectional"))
    )
    (net (code "62") (name "unconnected-(U2D-PA15-Pad50)") (class "Default")
      (node (ref "U2") (pin "50") (pinfunction "PA15_50") (pintype "bidirectional"))
    )
    (net (code "63") (name "unconnected-(U2D-PB4-Pad56)") (class "Default")
      (node (ref "U2") (pin "56") (pinfunction "PB4_56") (pintype "bidirectional"))
    )
    (net (code "64") (name "unconnected-(U2D-PD2-Pad54)") (class "Default")
      (node (ref "U2") (pin "54") (pinfunction "PD2_54") (pintype "bidirectional"))
    )
    (net (code "65") (name "unconnected-(U2F-PH1_OSC_OUT-Pad6)") (class "Default")
      (node (ref "U2") (pin "6") (pinfunction "PH1_OSC_OUT_6") (pintype "bidirectional"))
    )
    (net (code "66") (name "unconnected-(USB1-ID-Pad4)") (class "Default")
      (node (ref "USB1") (pin "4") (pinfunction "ID_4") (pintype "passive"))
    )
  )
)
